# MacroRail.net
KiCad netlist of a schematic drawn in EAGLE
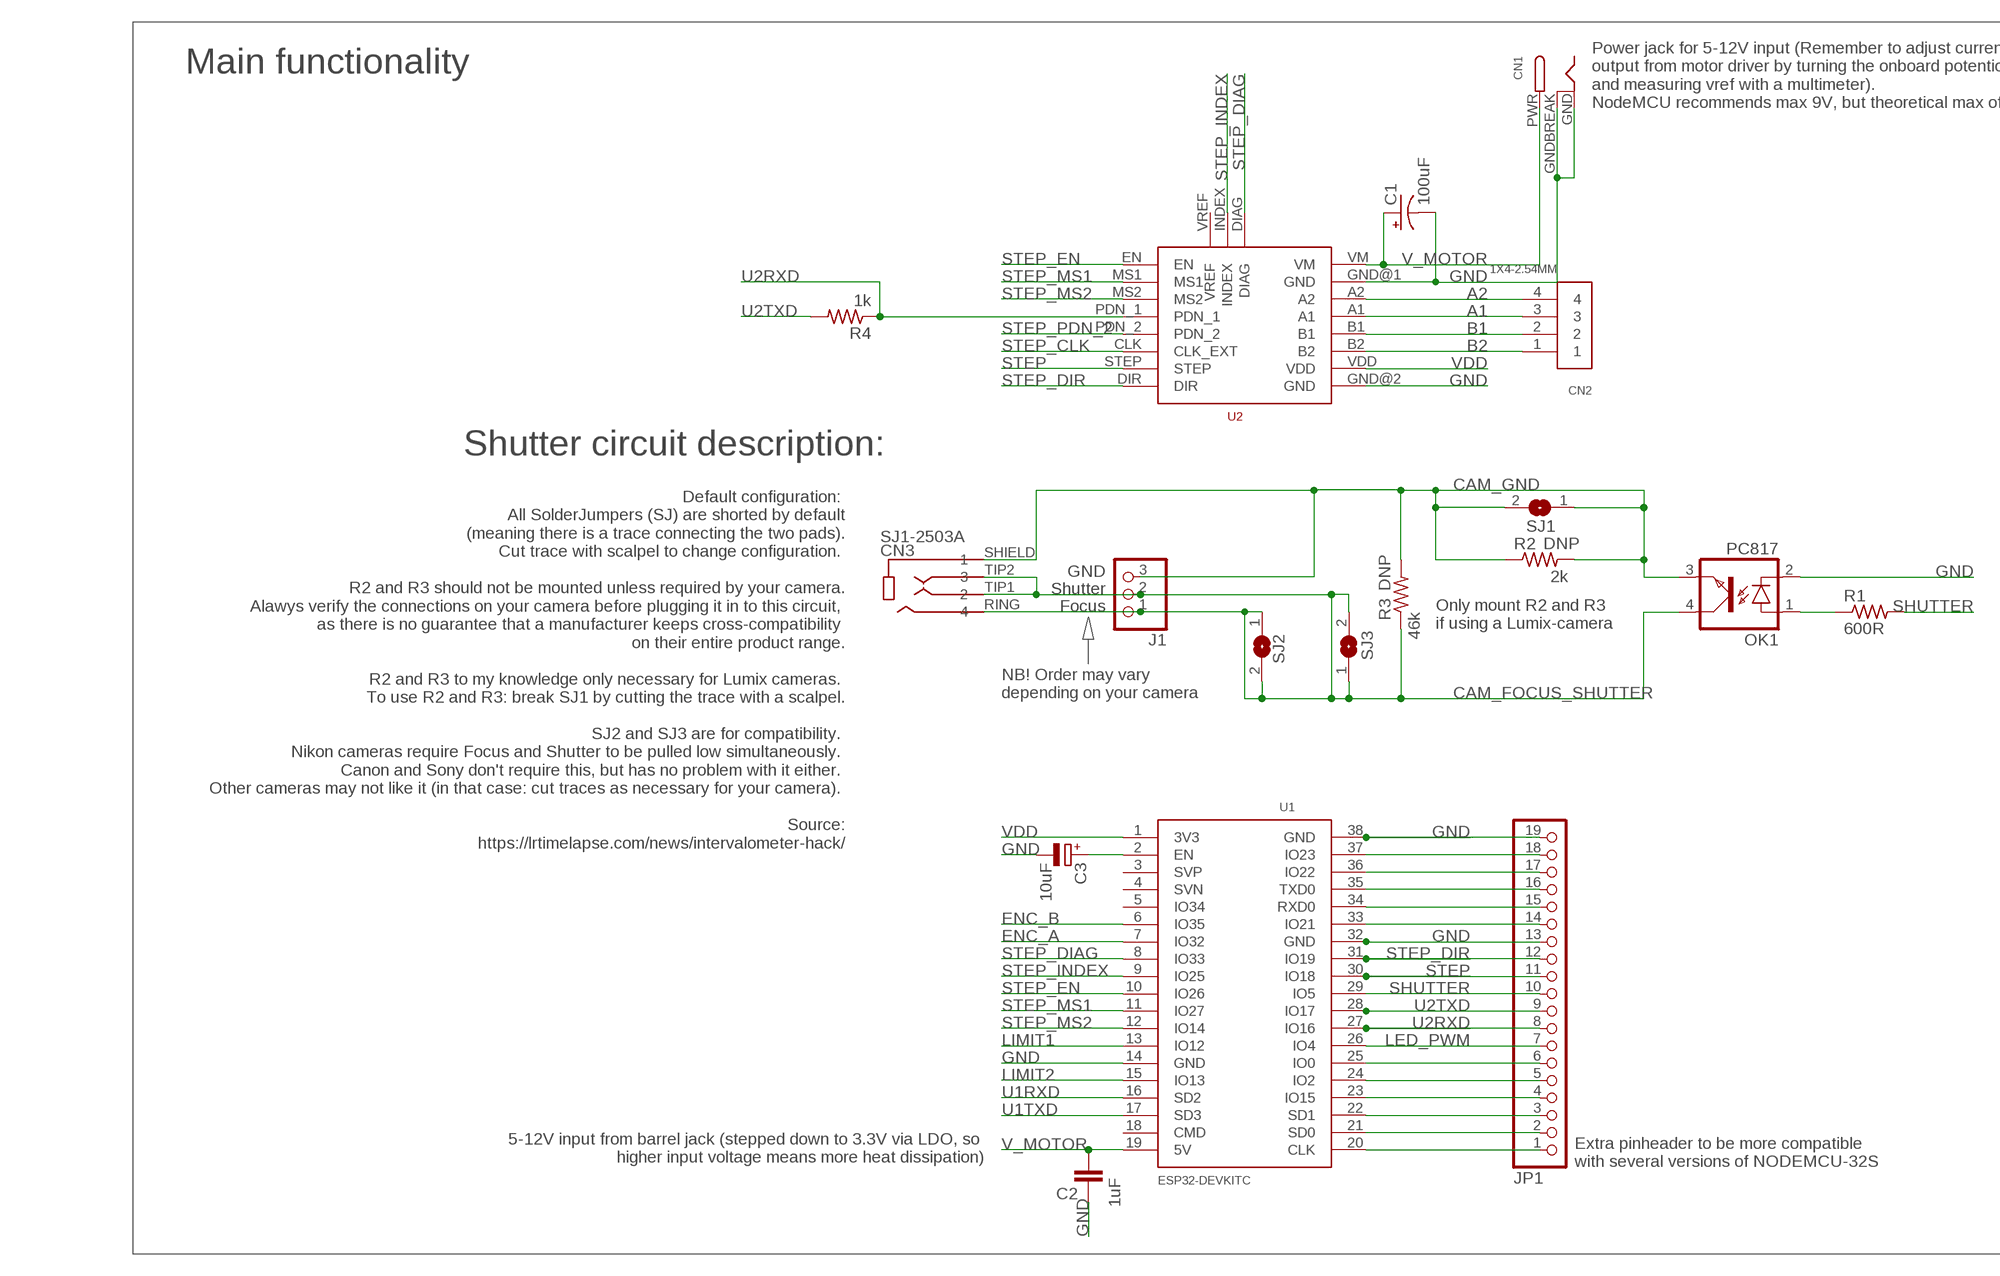
[diagram p0: schematic, sheet 1, part 1 of 2]
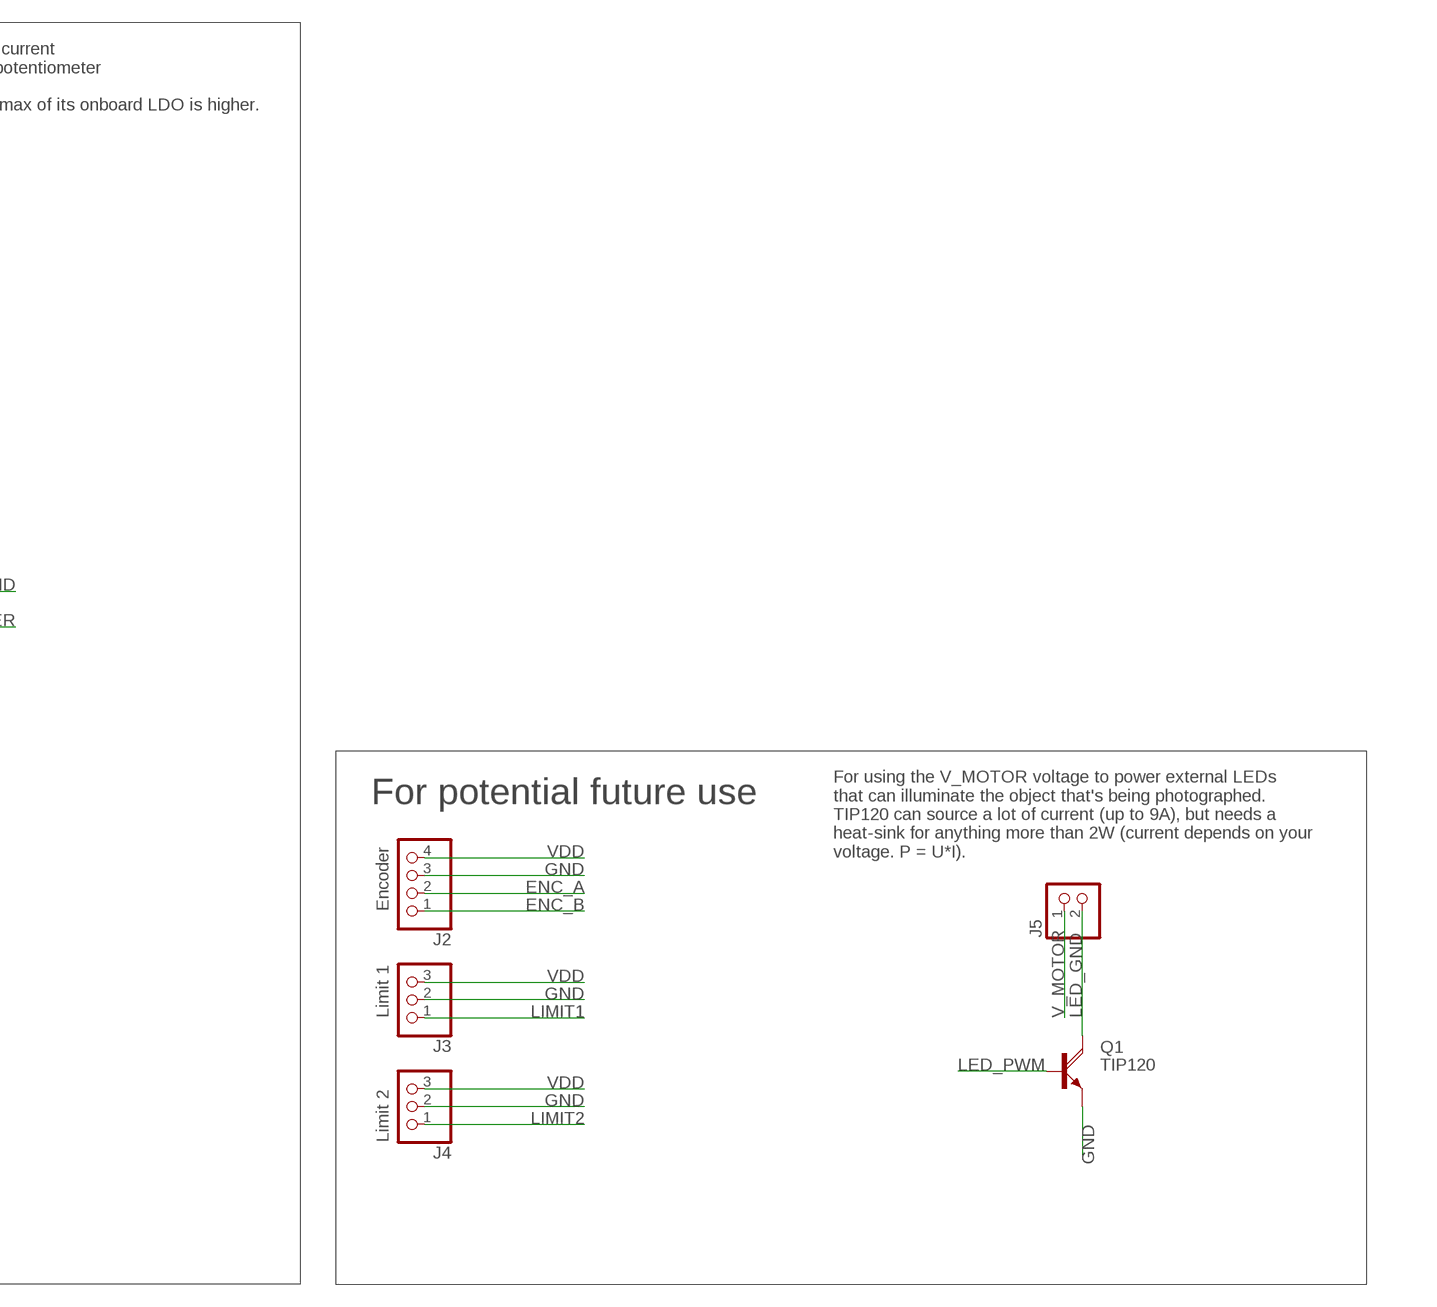
[diagram p1: schematic, sheet 1, part 2 of 2]

(export (version "E")
  (design (tool "Eeschema 10.0.6"))
  (components
    (comp (ref "C1")
      (value "100uF")
      (footprint "eagle-import:E5-8,5")
      (libsource (lib "eagle-import") (part "CPOL-USE5-8.5"))
    )
    (comp (ref "C2")
      (value "1uF")
      (footprint "eagle-import:C050-024X044")
      (libsource (lib "eagle-import") (part "C-EU050-024X044"))
    )
    (comp (ref "C3")
      (value "10uF")
      (footprint "eagle-import:E1,8-4")
      (libsource (lib "eagle-import") (part "CPOL-EUE1.8-4"))
    )
    (comp (ref "CN1")
      (value "DCBARRELPTH")
      (footprint "eagle-import:DCJACK_2MM_PTH")
      (libsource (lib "eagle-import") (part "DCBARRELPTH"))
    )
    (comp (ref "CN2")
      (value "1X4-2.54MM")
      (footprint "eagle-import:1X04-2.54MM")
      (libsource (lib "eagle-import") (part "1X4-2.54MM"))
    )
    (comp (ref "CN3")
      (value "SJ1-2503A")
      (footprint "eagle-import:STEREOJACK2.5MM_STEREOJACK2.5MM")
      (libsource (lib "eagle-import") (part "SJ1-2503A"))
    )
    (comp (ref "J1")
      (value "PINHD-1X3CB")
      (footprint "eagle-import:1X03-CLEANBIG")
      (libsource (lib "eagle-import") (part "PINHD-1X3CB"))
    )
    (comp (ref "J2")
      (value "PINHD-1X4")
      (footprint "eagle-import:1X04")
      (libsource (lib "eagle-import") (part "PINHD-1X4"))
    )
    (comp (ref "J3")
      (value "PINHD-1X3CB")
      (footprint "eagle-import:1X03-CLEANBIG")
      (libsource (lib "eagle-import") (part "PINHD-1X3CB"))
    )
    (comp (ref "J4")
      (value "PINHD-1X3CB")
      (footprint "eagle-import:1X03-CLEANBIG")
      (libsource (lib "eagle-import") (part "PINHD-1X3CB"))
    )
    (comp (ref "J5")
      (value "PINHD-1X2CLEAN")
      (footprint "eagle-import:1X02CLEAN")
      (libsource (lib "eagle-import") (part "PINHD-1X2CLEAN"))
    )
    (comp (ref "JP1")
      (value "PINHD-1X19")
      (footprint "eagle-import:1X19")
      (libsource (lib "eagle-import") (part "PINHD-1X19"))
    )
    (comp (ref "OK1")
      (value "PC817")
      (footprint "eagle-import:DIL04")
      (fields (field (name "MPN") "PC817X4J000F"))
      (libsource (lib "eagle-import") (part "PC817"))
    )
    (comp (ref "Q1")
      (value "TIP120")
      (footprint "eagle-import:TO220AH")
      (libsource (lib "eagle-import") (part "TIP120"))
    )
    (comp (ref "R1")
      (value "600R")
      (footprint "eagle-import:0207_7")
      (libsource (lib "eagle-import") (part "R-US_0207/7"))
    )
    (comp (ref "R2")
      (value "2k")
      (footprint "eagle-import:0207_7")
      (libsource (lib "eagle-import") (part "R-US_0207/7"))
    )
    (comp (ref "R3")
      (value "46k")
      (footprint "eagle-import:0207_7")
      (libsource (lib "eagle-import") (part "R-US_0207/7"))
    )
    (comp (ref "R4")
      (value "1k")
      (footprint "eagle-import:0207_7")
      (libsource (lib "eagle-import") (part "R-US_0207/7"))
    )
    (comp (ref "SJ1") (value "SJ") (footprint "eagle-import:SJ") (libsource (lib "eagle-import") (part "SJ")))
    (comp (ref "SJ2") (value "SJ") (footprint "eagle-import:SJ") (libsource (lib "eagle-import") (part "SJ")))
    (comp (ref "SJ3") (value "SJ") (footprint "eagle-import:SJ") (libsource (lib "eagle-import") (part "SJ")))
    (comp (ref "U1")
      (value "ESP32DEVKITCWIDE")
      (footprint "eagle-import:NODEMCU-32S")
      (libsource (lib "eagle-import") (part "ESP32DEVKITCWIDE"))
    )
    (comp (ref "U2")
      (value "TMC2209-V1.2+INDEX")
      (footprint "eagle-import:BIGTREETECH-TMC2209-V1.2+INDEX")
      (libsource (lib "eagle-import") (part "TMC2209-V1.2+INDEX"))
    )
  )
  (nets
    (net (code "1") (name "/A1") (class "Default")
      (node (ref "CN2") (pin "3") (pinfunction "3_3") (pintype "bidirectional"))
      (node (ref "U2") (pin "A1") (pinfunction "A1_A1") (pintype "bidirectional"))
    )
    (net (code "2") (name "/A2") (class "Default")
      (node (ref "CN2") (pin "4") (pinfunction "4_4") (pintype "bidirectional"))
      (node (ref "U2") (pin "A2") (pinfunction "A2_A2") (pintype "bidirectional"))
    )
    (net (code "3") (name "/B1") (class "Default")
      (node (ref "CN2") (pin "2") (pinfunction "2_2") (pintype "bidirectional"))
      (node (ref "U2") (pin "B1") (pinfunction "B1_B1") (pintype "bidirectional"))
    )
    (net (code "4") (name "/B2") (class "Default")
      (node (ref "CN2") (pin "1") (pinfunction "1_1") (pintype "bidirectional"))
      (node (ref "U2") (pin "B2") (pinfunction "B2_B2") (pintype "bidirectional"))
    )
    (net (code "5") (name "/CAM_FOCUS_SHUTTER") (class "Default")
      (node (ref "CN3") (pin "RING") (pinfunction "4_RING") (pintype "bidirectional"))
      (node (ref "CN3") (pin "TIP1") (pinfunction "2_TIP1") (pintype "bidirectional"))
      (node (ref "CN3") (pin "TIP2") (pinfunction "3_TIP2") (pintype "bidirectional"))
      (node (ref "J1") (pin "1") (pinfunction "1_1") (pintype "passive"))
      (node (ref "J1") (pin "2") (pinfunction "2_2") (pintype "passive"))
      (node (ref "OK1") (pin "4") (pinfunction "COL_4") (pintype "passive"))
      (node (ref "R3") (pin "1") (pinfunction "1_1") (pintype "passive"))
      (node (ref "SJ2") (pin "1") (pinfunction "1_1") (pintype "passive"))
      (node (ref "SJ2") (pin "2") (pinfunction "2_2") (pintype "passive"))
      (node (ref "SJ3") (pin "1") (pinfunction "1_1") (pintype "passive"))
      (node (ref "SJ3") (pin "2") (pinfunction "2_2") (pintype "passive"))
    )
    (net (code "6") (name "/CAM_GND") (class "Default")
      (node (ref "CN3") (pin "SHIELD") (pinfunction "1_SHIELD") (pintype "bidirectional"))
      (node (ref "J1") (pin "3") (pinfunction "3_3") (pintype "passive"))
      (node (ref "OK1") (pin "3") (pinfunction "EMIT_3") (pintype "passive"))
      (node (ref "R2") (pin "1") (pinfunction "1_1") (pintype "passive"))
      (node (ref "R2") (pin "2") (pinfunction "2_2") (pintype "passive"))
      (node (ref "R3") (pin "2") (pinfunction "2_2") (pintype "passive"))
      (node (ref "SJ1") (pin "1") (pinfunction "1_1") (pintype "passive"))
      (node (ref "SJ1") (pin "2") (pinfunction "2_2") (pintype "passive"))
    )
    (net (code "7") (name "/ENC_A") (class "Default")
      (node (ref "J2") (pin "2") (pinfunction "2_2") (pintype "passive"))
      (node (ref "U1") (pin "7") (pinfunction "IO32_7") (pintype "bidirectional"))
    )
    (net (code "8") (name "/ENC_B") (class "Default")
      (node (ref "J2") (pin "1") (pinfunction "1_1") (pintype "passive"))
      (node (ref "U1") (pin "6") (pinfunction "IO35_6") (pintype "bidirectional"))
    )
    (net (code "9") (name "/GND") (class "Default")
      (node (ref "C1") (pin "-") (pinfunction "-_-") (pintype "passive"))
      (node (ref "C2") (pin "1") (pinfunction "1_1") (pintype "passive"))
      (node (ref "C3") (pin "-") (pinfunction "-_-") (pintype "passive"))
      (node (ref "CN1") (pin "GND") (pinfunction "GND_GND") (pintype "power_in"))
      (node (ref "CN1") (pin "GNDBREAK") (pinfunction "GNDBREAK_GNDBREAK") (pintype "power_in"))
      (node (ref "J2") (pin "3") (pinfunction "3_3") (pintype "passive"))
      (node (ref "J3") (pin "2") (pinfunction "2_2") (pintype "passive"))
      (node (ref "J4") (pin "2") (pinfunction "2_2") (pintype "passive"))
      (node (ref "JP1") (pin "13") (pinfunction "13_13") (pintype "passive"))
      (node (ref "JP1") (pin "19") (pinfunction "19_19") (pintype "passive"))
      (node (ref "OK1") (pin "2") (pinfunction "C_2") (pintype "passive"))
      (node (ref "Q1") (pin "E") (pinfunction "E_E") (pintype "passive"))
      (node (ref "U1") (pin "14") (pinfunction "GND_14") (pintype "bidirectional"))
      (node (ref "U1") (pin "32") (pinfunction "GND_32") (pintype "bidirectional"))
      (node (ref "U1") (pin "38") (pinfunction "GND_38") (pintype "bidirectional"))
      (node (ref "U2") (pin "GND@1") (pinfunction "GND_GND@1") (pintype "bidirectional"))
      (node (ref "U2") (pin "GND@2") (pinfunction "GND_GND@2") (pintype "bidirectional"))
    )
    (net (code "10") (name "/LED_GND") (class "Default")
      (node (ref "J5") (pin "2") (pinfunction "2_2") (pintype "passive"))
      (node (ref "Q1") (pin "C") (pinfunction "C_C") (pintype "passive"))
    )
    (net (code "11") (name "/LED_PWM") (class "Default")
      (node (ref "JP1") (pin "7") (pinfunction "7_7") (pintype "passive"))
      (node (ref "Q1") (pin "B") (pinfunction "B_B") (pintype "passive"))
      (node (ref "U1") (pin "26") (pinfunction "IO4_26") (pintype "bidirectional"))
    )
    (net (code "12") (name "/LIMIT1") (class "Default")
      (node (ref "J3") (pin "1") (pinfunction "1_1") (pintype "passive"))
      (node (ref "U1") (pin "13") (pinfunction "IO12_13") (pintype "bidirectional"))
    )
    (net (code "13") (name "/LIMIT2") (class "Default")
      (node (ref "J4") (pin "1") (pinfunction "1_1") (pintype "passive"))
      (node (ref "U1") (pin "15") (pinfunction "IO13_15") (pintype "bidirectional"))
    )
    (net (code "14") (name "/SHUTTER") (class "Default")
      (node (ref "JP1") (pin "10") (pinfunction "10_10") (pintype "passive"))
      (node (ref "R1") (pin "2") (pinfunction "2_2") (pintype "passive"))
      (node (ref "U1") (pin "29") (pinfunction "IO5_29") (pintype "bidirectional"))
    )
    (net (code "15") (name "/STEP") (class "Default")
      (node (ref "JP1") (pin "11") (pinfunction "11_11") (pintype "passive"))
      (node (ref "U1") (pin "30") (pinfunction "IO18_30") (pintype "bidirectional"))
      (node (ref "U2") (pin "STEP") (pinfunction "STEP_STEP") (pintype "bidirectional"))
    )
    (net (code "16") (name "/STEP_CLK") (class "Default")
      (node (ref "U2") (pin "CLK") (pinfunction "CLK_EXT_CLK") (pintype "bidirectional"))
    )
    (net (code "17") (name "/STEP_DIAG") (class "Default")
      (node (ref "U1") (pin "8") (pinfunction "IO33_8") (pintype "bidirectional"))
      (node (ref "U2") (pin "DIAG") (pinfunction "DIAG_DIAG") (pintype "bidirectional"))
    )
    (net (code "18") (name "/STEP_DIR") (class "Default")
      (node (ref "JP1") (pin "12") (pinfunction "12_12") (pintype "passive"))
      (node (ref "U1") (pin "31") (pinfunction "IO19_31") (pintype "bidirectional"))
      (node (ref "U2") (pin "DIR") (pinfunction "DIR_DIR") (pintype "bidirectional"))
    )
    (net (code "19") (name "/STEP_EN") (class "Default")
      (node (ref "U1") (pin "10") (pinfunction "IO26_10") (pintype "bidirectional"))
      (node (ref "U2") (pin "EN") (pinfunction "EN_EN") (pintype "bidirectional"))
    )
    (net (code "20") (name "/STEP_INDEX") (class "Default")
      (node (ref "U1") (pin "9") (pinfunction "IO25_9") (pintype "bidirectional"))
      (node (ref "U2") (pin "INDEX") (pinfunction "INDEX_INDEX") (pintype "bidirectional"))
    )
    (net (code "21") (name "/STEP_MS1") (class "Default")
      (node (ref "U1") (pin "11") (pinfunction "IO27_11") (pintype "bidirectional"))
      (node (ref "U2") (pin "MS1") (pinfunction "MS1_MS1") (pintype "bidirectional"))
    )
    (net (code "22") (name "/STEP_MS2") (class "Default")
      (node (ref "U1") (pin "12") (pinfunction "IO14_12") (pintype "bidirectional"))
      (node (ref "U2") (pin "MS2") (pinfunction "MS2_MS2") (pintype "bidirectional"))
    )
    (net (code "23") (name "/STEP_PDN_2") (class "Default")
      (node (ref "U2") (pin "PDN_2") (pinfunction "PDN_2_PDN_2") (pintype "bidirectional"))
    )
    (net (code "24") (name "/U1RXD") (class "Default")
      (node (ref "U1") (pin "16") (pinfunction "SD2_16") (pintype "bidirectional"))
    )
    (net (code "25") (name "/U1TXD") (class "Default")
      (node (ref "U1") (pin "17") (pinfunction "SD3_17") (pintype "bidirectional"))
    )
    (net (code "26") (name "/U2RXD") (class "Default")
      (node (ref "JP1") (pin "8") (pinfunction "8_8") (pintype "passive"))
      (node (ref "R4") (pin "1") (pinfunction "1_1") (pintype "passive"))
      (node (ref "U1") (pin "27") (pinfunction "IO16_27") (pintype "bidirectional"))
      (node (ref "U2") (pin "PDN_1") (pinfunction "PDN_1_PDN_1") (pintype "bidirectional"))
    )
    (net (code "27") (name "/U2TXD") (class "Default")
      (node (ref "JP1") (pin "9") (pinfunction "9_9") (pintype "passive"))
      (node (ref "R4") (pin "2") (pinfunction "2_2") (pintype "passive"))
      (node (ref "U1") (pin "28") (pinfunction "IO17_28") (pintype "bidirectional"))
    )
    (net (code "28") (name "/VDD") (class "Default")
      (node (ref "J2") (pin "4") (pinfunction "4_4") (pintype "passive"))
      (node (ref "J3") (pin "3") (pinfunction "3_3") (pintype "passive"))
      (node (ref "J4") (pin "3") (pinfunction "3_3") (pintype "passive"))
      (node (ref "U1") (pin "1") (pinfunction "3V3_1") (pintype "bidirectional"))
      (node (ref "U2") (pin "VDD") (pinfunction "VDD_VDD") (pintype "bidirectional"))
    )
    (net (code "29") (name "/V_MOTOR") (class "Default")
      (node (ref "C1") (pin "+") (pinfunction "+_+") (pintype "passive"))
      (node (ref "C2") (pin "2") (pinfunction "2_2") (pintype "passive"))
      (node (ref "CN1") (pin "PWR") (pinfunction "PWR_PWR") (pintype "power_in"))
      (node (ref "J5") (pin "1") (pinfunction "1_1") (pintype "passive"))
      (node (ref "U1") (pin "19") (pinfunction "5V_19") (pintype "bidirectional"))
      (node (ref "U2") (pin "VM") (pinfunction "VM_VM") (pintype "bidirectional"))
    )
    (net (code "30") (name "Net-(OK1-A)") (class "Default")
      (node (ref "OK1") (pin "1") (pinfunction "A_1") (pintype "passive"))
      (node (ref "R1") (pin "1") (pinfunction "1_1") (pintype "passive"))
    )
    (net (code "31") (name "Net-(U1-CLK)") (class "Default")
      (node (ref "JP1") (pin "1") (pinfunction "1_1") (pintype "passive"))
      (node (ref "U1") (pin "20") (pinfunction "CLK_20") (pintype "bidirectional"))
    )
    (net (code "32") (name "Net-(U1-EN)") (class "Default")
      (node (ref "C3") (pin "+") (pinfunction "+_+") (pintype "passive"))
      (node (ref "U1") (pin "2") (pinfunction "EN_2") (pintype "bidirectional"))
    )
    (net (code "33") (name "Net-(U1-IO0)") (class "Default")
      (node (ref "JP1") (pin "6") (pinfunction "6_6") (pintype "passive"))
      (node (ref "U1") (pin "25") (pinfunction "IO0_25") (pintype "bidirectional"))
    )
    (net (code "34") (name "Net-(U1-IO2)") (class "Default")
      (node (ref "JP1") (pin "5") (pinfunction "5_5") (pintype "passive"))
      (node (ref "U1") (pin "24") (pinfunction "IO2_24") (pintype "bidirectional"))
    )
    (net (code "35") (name "Net-(U1-IO15)") (class "Default")
      (node (ref "JP1") (pin "4") (pinfunction "4_4") (pintype "passive"))
      (node (ref "U1") (pin "23") (pinfunction "IO15_23") (pintype "bidirectional"))
    )
    (net (code "36") (name "Net-(U1-IO21)") (class "Default")
      (node (ref "JP1") (pin "14") (pinfunction "14_14") (pintype "passive"))
      (node (ref "U1") (pin "33") (pinfunction "IO21_33") (pintype "bidirectional"))
    )
    (net (code "37") (name "Net-(U1-IO22)") (class "Default")
      (node (ref "JP1") (pin "17") (pinfunction "17_17") (pintype "passive"))
      (node (ref "U1") (pin "36") (pinfunction "IO22_36") (pintype "bidirectional"))
    )
    (net (code "38") (name "Net-(U1-IO23)") (class "Default")
      (node (ref "JP1") (pin "18") (pinfunction "18_18") (pintype "passive"))
      (node (ref "U1") (pin "37") (pinfunction "IO23_37") (pintype "bidirectional"))
    )
    (net (code "39") (name "Net-(U1-RXD0)") (class "Default")
      (node (ref "JP1") (pin "15") (pinfunction "15_15") (pintype "passive"))
      (node (ref "U1") (pin "34") (pinfunction "RXD0_34") (pintype "bidirectional"))
    )
    (net (code "40") (name "Net-(U1-SD0)") (class "Default")
      (node (ref "JP1") (pin "2") (pinfunction "2_2") (pintype "passive"))
      (node (ref "U1") (pin "21") (pinfunction "SD0_21") (pintype "bidirectional"))
    )
    (net (code "41") (name "Net-(U1-SD1)") (class "Default")
      (node (ref "JP1") (pin "3") (pinfunction "3_3") (pintype "passive"))
      (node (ref "U1") (pin "22") (pinfunction "SD1_22") (pintype "bidirectional"))
    )
    (net (code "42") (name "Net-(U1-TXD0)") (class "Default")
      (node (ref "JP1") (pin "16") (pinfunction "16_16") (pintype "passive"))
      (node (ref "U1") (pin "35") (pinfunction "TXD0_35") (pintype "bidirectional"))
    )
    (net (code "43") (name "unconnected-(U1-CMD-Pad18)") (class "Default")
      (node (ref "U1") (pin "18") (pinfunction "CMD_18") (pintype "bidirectional"))
    )
    (net (code "44") (name "unconnected-(U1-IO34-Pad5)") (class "Default")
      (node (ref "U1") (pin "5") (pinfunction "IO34_5") (pintype "bidirectional"))
    )
    (net (code "45") (name "unconnected-(U1-SVN-Pad4)") (class "Default")
      (node (ref "U1") (pin "4") (pinfunction "SVN_4") (pintype "bidirectional"))
    )
    (net (code "46") (name "unconnected-(U1-SVP-Pad3)") (class "Default")
      (node (ref "U1") (pin "3") (pinfunction "SVP_3") (pintype "bidirectional"))
    )
    (net (code "47") (name "unconnected-(U2-PadVREF)") (class "Default")
      (node (ref "U2") (pin "VREF") (pinfunction "VREF_VREF") (pintype "bidirectional"))
    )
  )
)
